# wordclock_final.net
KiCad netlist of a schematic drawn in EAGLE
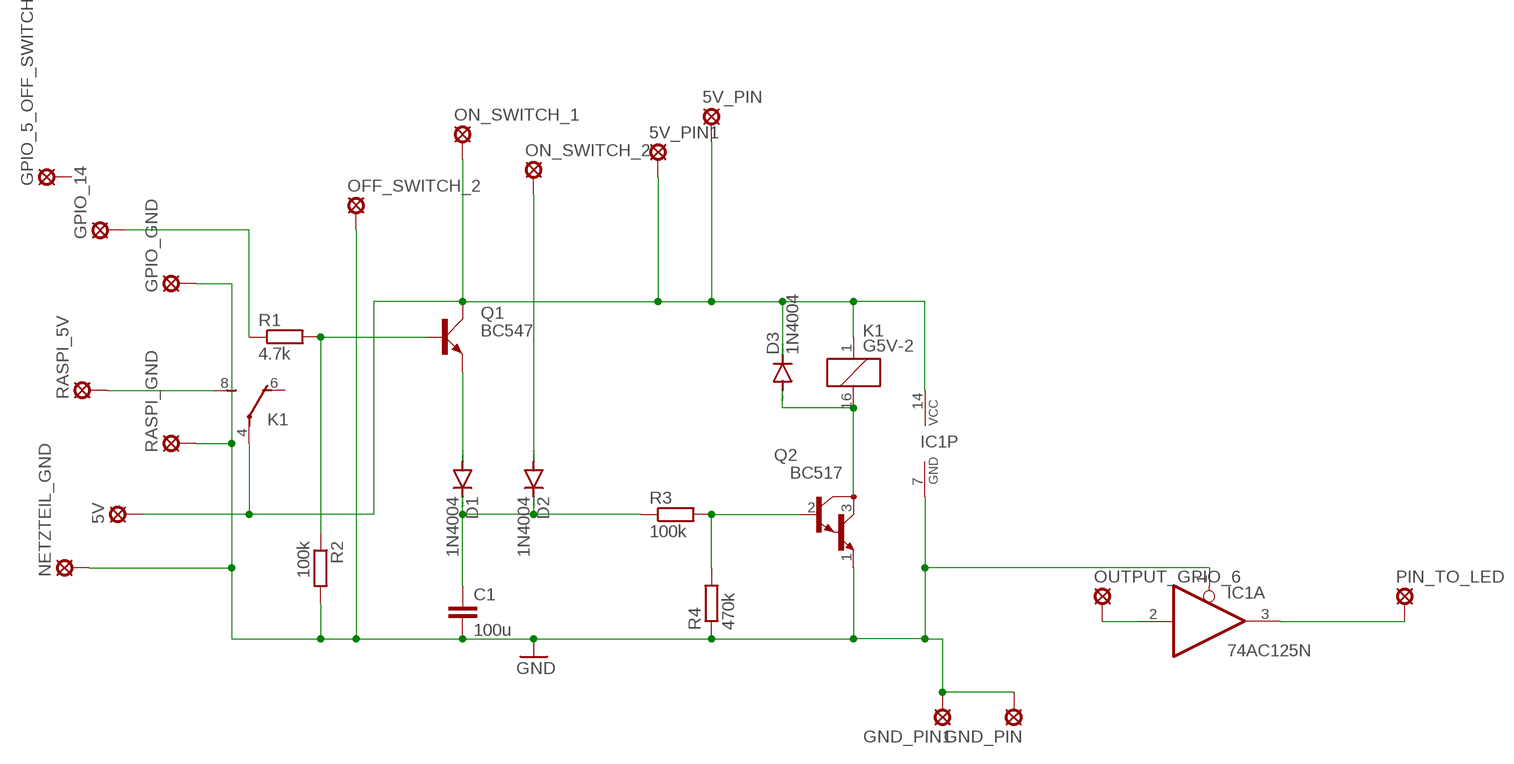
[diagram p0: schematic, sheet 1]

(export (version "E")
  (design (tool "Eeschema 10.0.6"))
  (components
    (comp (ref "5V")
      (value "SE14")
      (footprint "eagle-import:SE14")
      (libsource (lib "eagle-import") (part "SE14"))
    )
    (comp (ref "5V_PIN")
      (value "SE14")
      (footprint "eagle-import:SE14")
      (libsource (lib "eagle-import") (part "SE14"))
    )
    (comp (ref "5V_PIN1")
      (value "SE14")
      (footprint "eagle-import:SE14")
      (libsource (lib "eagle-import") (part "SE14"))
    )
    (comp (ref "C1")
      (value "100u")
      (footprint "eagle-import:C025-060X050")
      (libsource (lib "eagle-import") (part "C-EU025-060X050"))
    )
    (comp (ref "D1")
      (value "1N4004")
      (footprint "eagle-import:DO41-10")
      (libsource (lib "eagle-import") (part "1N4004"))
    )
    (comp (ref "D2")
      (value "1N4004")
      (footprint "eagle-import:DO41-10")
      (libsource (lib "eagle-import") (part "1N4004"))
    )
    (comp (ref "D3")
      (value "1N4004")
      (footprint "eagle-import:DO41-10")
      (libsource (lib "eagle-import") (part "1N4004"))
    )
    (comp (ref "GND_PIN")
      (value "SE14")
      (footprint "eagle-import:SE14")
      (libsource (lib "eagle-import") (part "SE14"))
    )
    (comp (ref "GND_PIN1")
      (value "SE14")
      (footprint "eagle-import:SE14")
      (libsource (lib "eagle-import") (part "SE14"))
    )
    (comp (ref "GPIO_5_OFF_SWITCH")
      (value "SE14")
      (footprint "eagle-import:SE14")
      (libsource (lib "eagle-import") (part "SE14"))
    )
    (comp (ref "GPIO_14")
      (value "SE14")
      (footprint "eagle-import:SE14")
      (libsource (lib "eagle-import") (part "SE14"))
    )
    (comp (ref "GPIO_GND")
      (value "SE14")
      (footprint "eagle-import:SE14")
      (libsource (lib "eagle-import") (part "SE14"))
    )
    (comp (ref "IC1")
      (value "74AC125N")
      (footprint "eagle-import:DIL14")
      (libsource (lib "eagle-import") (part "74125NAC"))
    )
    (comp (ref "K1")
      (value "G5V-2")
      (footprint "eagle-import:G5V-2")
      (fields (field (name "MPN") "G5V-2 5DC"))
      (libsource (lib "eagle-import") (part "G5V-2"))
    )
    (comp (ref "NETZTEIL_GND")
      (value "SE14")
      (footprint "eagle-import:SE14")
      (libsource (lib "eagle-import") (part "SE14"))
    )
    (comp (ref "OFF_SWITCH_2")
      (value "SE14")
      (footprint "eagle-import:SE14")
      (libsource (lib "eagle-import") (part "SE14"))
    )
    (comp (ref "ON_SWITCH_1")
      (value "SE14")
      (footprint "eagle-import:SE14")
      (libsource (lib "eagle-import") (part "SE14"))
    )
    (comp (ref "ON_SWITCH_2")
      (value "SE14")
      (footprint "eagle-import:SE14")
      (libsource (lib "eagle-import") (part "SE14"))
    )
    (comp (ref "OUTPUT_GPIO_6")
      (value "SE14")
      (footprint "eagle-import:SE14")
      (libsource (lib "eagle-import") (part "SE14"))
    )
    (comp (ref "PIN_TO_LED")
      (value "SE14")
      (footprint "eagle-import:SE14")
      (libsource (lib "eagle-import") (part "SE14"))
    )
    (comp (ref "Q1")
      (value "BC547")
      (footprint "eagle-import:SOT54A")
      (libsource (lib "eagle-import") (part "BC547"))
    )
    (comp (ref "Q2")
      (value "BC517")
      (footprint "eagle-import:TO92")
      (libsource (lib "eagle-import") (part "BC517"))
    )
    (comp (ref "R1")
      (value "4.7k")
      (footprint "eagle-import:0207_10")
      (libsource (lib "eagle-import") (part "R-EU_0207/10"))
    )
    (comp (ref "R2")
      (value "100k")
      (footprint "eagle-import:0207_10")
      (libsource (lib "eagle-import") (part "R-EU_0207/10"))
    )
    (comp (ref "R3")
      (value "100k")
      (footprint "eagle-import:0207_10")
      (libsource (lib "eagle-import") (part "R-EU_0207/10"))
    )
    (comp (ref "R4")
      (value "470k")
      (footprint "eagle-import:0207_10")
      (libsource (lib "eagle-import") (part "R-EU_0207/10"))
    )
    (comp (ref "RASPI_5V")
      (value "SE14")
      (footprint "eagle-import:SE14")
      (libsource (lib "eagle-import") (part "SE14"))
    )
    (comp (ref "RASPI_GND")
      (value "SE14")
      (footprint "eagle-import:SE14")
      (libsource (lib "eagle-import") (part "SE14"))
    )
  )
  (nets
    (net (code "1") (name "GND") (class "Default")
      (node (ref "C1") (pin "2") (pinfunction "2_2") (pintype "passive"))
      (node (ref "GND_PIN") (pin "MP") (pinfunction "MP_MP") (pintype "passive"))
      (node (ref "GND_PIN1") (pin "MP") (pinfunction "MP_MP") (pintype "passive"))
      (node (ref "GPIO_GND") (pin "MP") (pinfunction "MP_MP") (pintype "passive"))
      (node (ref "IC1") (pin "1") (pinfunction "OE_1") (pintype "input"))
      (node (ref "IC1") (pin "7") (pinfunction "GND_7") (pintype "power_in"))
      (node (ref "NETZTEIL_GND") (pin "MP") (pinfunction "MP_MP") (pintype "passive"))
      (node (ref "OFF_SWITCH_2") (pin "MP") (pinfunction "MP_MP") (pintype "passive"))
      (node (ref "Q2") (pin "1") (pinfunction "E_1") (pintype "passive"))
      (node (ref "R2") (pin "2") (pinfunction "2_2") (pintype "passive"))
      (node (ref "R4") (pin "1") (pinfunction "1_1") (pintype "passive"))
      (node (ref "RASPI_GND") (pin "MP") (pinfunction "MP_MP") (pintype "passive"))
    )
    (net (code "2") (name "Net-(C1-Pad1)") (class "Default")
      (node (ref "C1") (pin "1") (pinfunction "1_1") (pintype "passive"))
      (node (ref "D1") (pin "C") (pinfunction "C_C") (pintype "passive"))
      (node (ref "D2") (pin "C") (pinfunction "C_C") (pintype "passive"))
      (node (ref "R3") (pin "1") (pinfunction "1_1") (pintype "passive"))
    )
    (net (code "3") (name "Net-(D1-PadA)") (class "Default")
      (node (ref "D1") (pin "A") (pinfunction "A_A") (pintype "passive"))
      (node (ref "Q1") (pin "E") (pinfunction "E_E") (pintype "passive"))
    )
    (net (code "4") (name "Net-(D2-PadA)") (class "Default")
      (node (ref "D2") (pin "A") (pinfunction "A_A") (pintype "passive"))
      (node (ref "ON_SWITCH_2") (pin "MP") (pinfunction "MP_MP") (pintype "passive"))
    )
    (net (code "5") (name "Net-(GPIO_14-PadMP)") (class "Default")
      (node (ref "GPIO_14") (pin "MP") (pinfunction "MP_MP") (pintype "passive"))
      (node (ref "R1") (pin "1") (pinfunction "1_1") (pintype "passive"))
    )
    (net (code "6") (name "Net-(IC1A-I)") (class "Default")
      (node (ref "IC1") (pin "2") (pinfunction "I_2") (pintype "input"))
      (node (ref "OUTPUT_GPIO_6") (pin "MP") (pinfunction "MP_MP") (pintype "passive"))
    )
    (net (code "7") (name "Net-(IC1A-O)") (class "Default")
      (node (ref "IC1") (pin "3") (pinfunction "O_3") (pintype "tri_state"))
      (node (ref "PIN_TO_LED") (pin "MP") (pinfunction "MP_MP") (pintype "passive"))
    )
    (net (code "8") (name "Net-(IC1E-VCC)") (class "Default")
      (node (ref "5V") (pin "MP") (pinfunction "MP_MP") (pintype "passive"))
      (node (ref "5V_PIN") (pin "MP") (pinfunction "MP_MP") (pintype "passive"))
      (node (ref "5V_PIN1") (pin "MP") (pinfunction "MP_MP") (pintype "passive"))
      (node (ref "D3") (pin "C") (pinfunction "C_C") (pintype "passive"))
      (node (ref "IC1") (pin "14") (pinfunction "VCC_14") (pintype "power_in"))
      (node (ref "K1") (pin "1") (pinfunction "1_1") (pintype "passive"))
      (node (ref "K1") (pin "4") (pinfunction "P_4") (pintype "passive"))
      (node (ref "ON_SWITCH_1") (pin "MP") (pinfunction "MP_MP") (pintype "passive"))
      (node (ref "Q1") (pin "C") (pinfunction "C_C") (pintype "passive"))
    )
    (net (code "9") (name "Net-(K1A-S)") (class "Default")
      (node (ref "K1") (pin "8") (pinfunction "S_8") (pintype "passive"))
      (node (ref "RASPI_5V") (pin "MP") (pinfunction "MP_MP") (pintype "passive"))
    )
    (net (code "10") (name "Net-(K1C-2)") (class "Default")
      (node (ref "D3") (pin "A") (pinfunction "A_A") (pintype "passive"))
      (node (ref "K1") (pin "16") (pinfunction "2_16") (pintype "passive"))
      (node (ref "Q2") (pin "3") (pinfunction "C_3") (pintype "passive"))
    )
    (net (code "11") (name "Net-(Q1-PadB)") (class "Default")
      (node (ref "Q1") (pin "B") (pinfunction "B_B") (pintype "passive"))
      (node (ref "R1") (pin "2") (pinfunction "2_2") (pintype "passive"))
      (node (ref "R2") (pin "1") (pinfunction "1_1") (pintype "passive"))
    )
    (net (code "12") (name "Net-(Q2-B)") (class "Default")
      (node (ref "Q2") (pin "2") (pinfunction "B_2") (pintype "passive"))
      (node (ref "R3") (pin "2") (pinfunction "2_2") (pintype "passive"))
      (node (ref "R4") (pin "2") (pinfunction "2_2") (pintype "passive"))
    )
    (net (code "13") (name "unconnected-(GPIO_5_OFF_SWITCH-PadMP)") (class "Default")
      (node (ref "GPIO_5_OFF_SWITCH") (pin "MP") (pinfunction "MP_MP") (pintype "passive"))
    )
    (net (code "14") (name "unconnected-(K1A-O-Pad6)") (class "Default")
      (node (ref "K1") (pin "6") (pinfunction "O_6") (pintype "passive"))
    )
  )
)
